# Buisnesscard.net
KiCad netlist of a schematic drawn in EasyEDA Pro
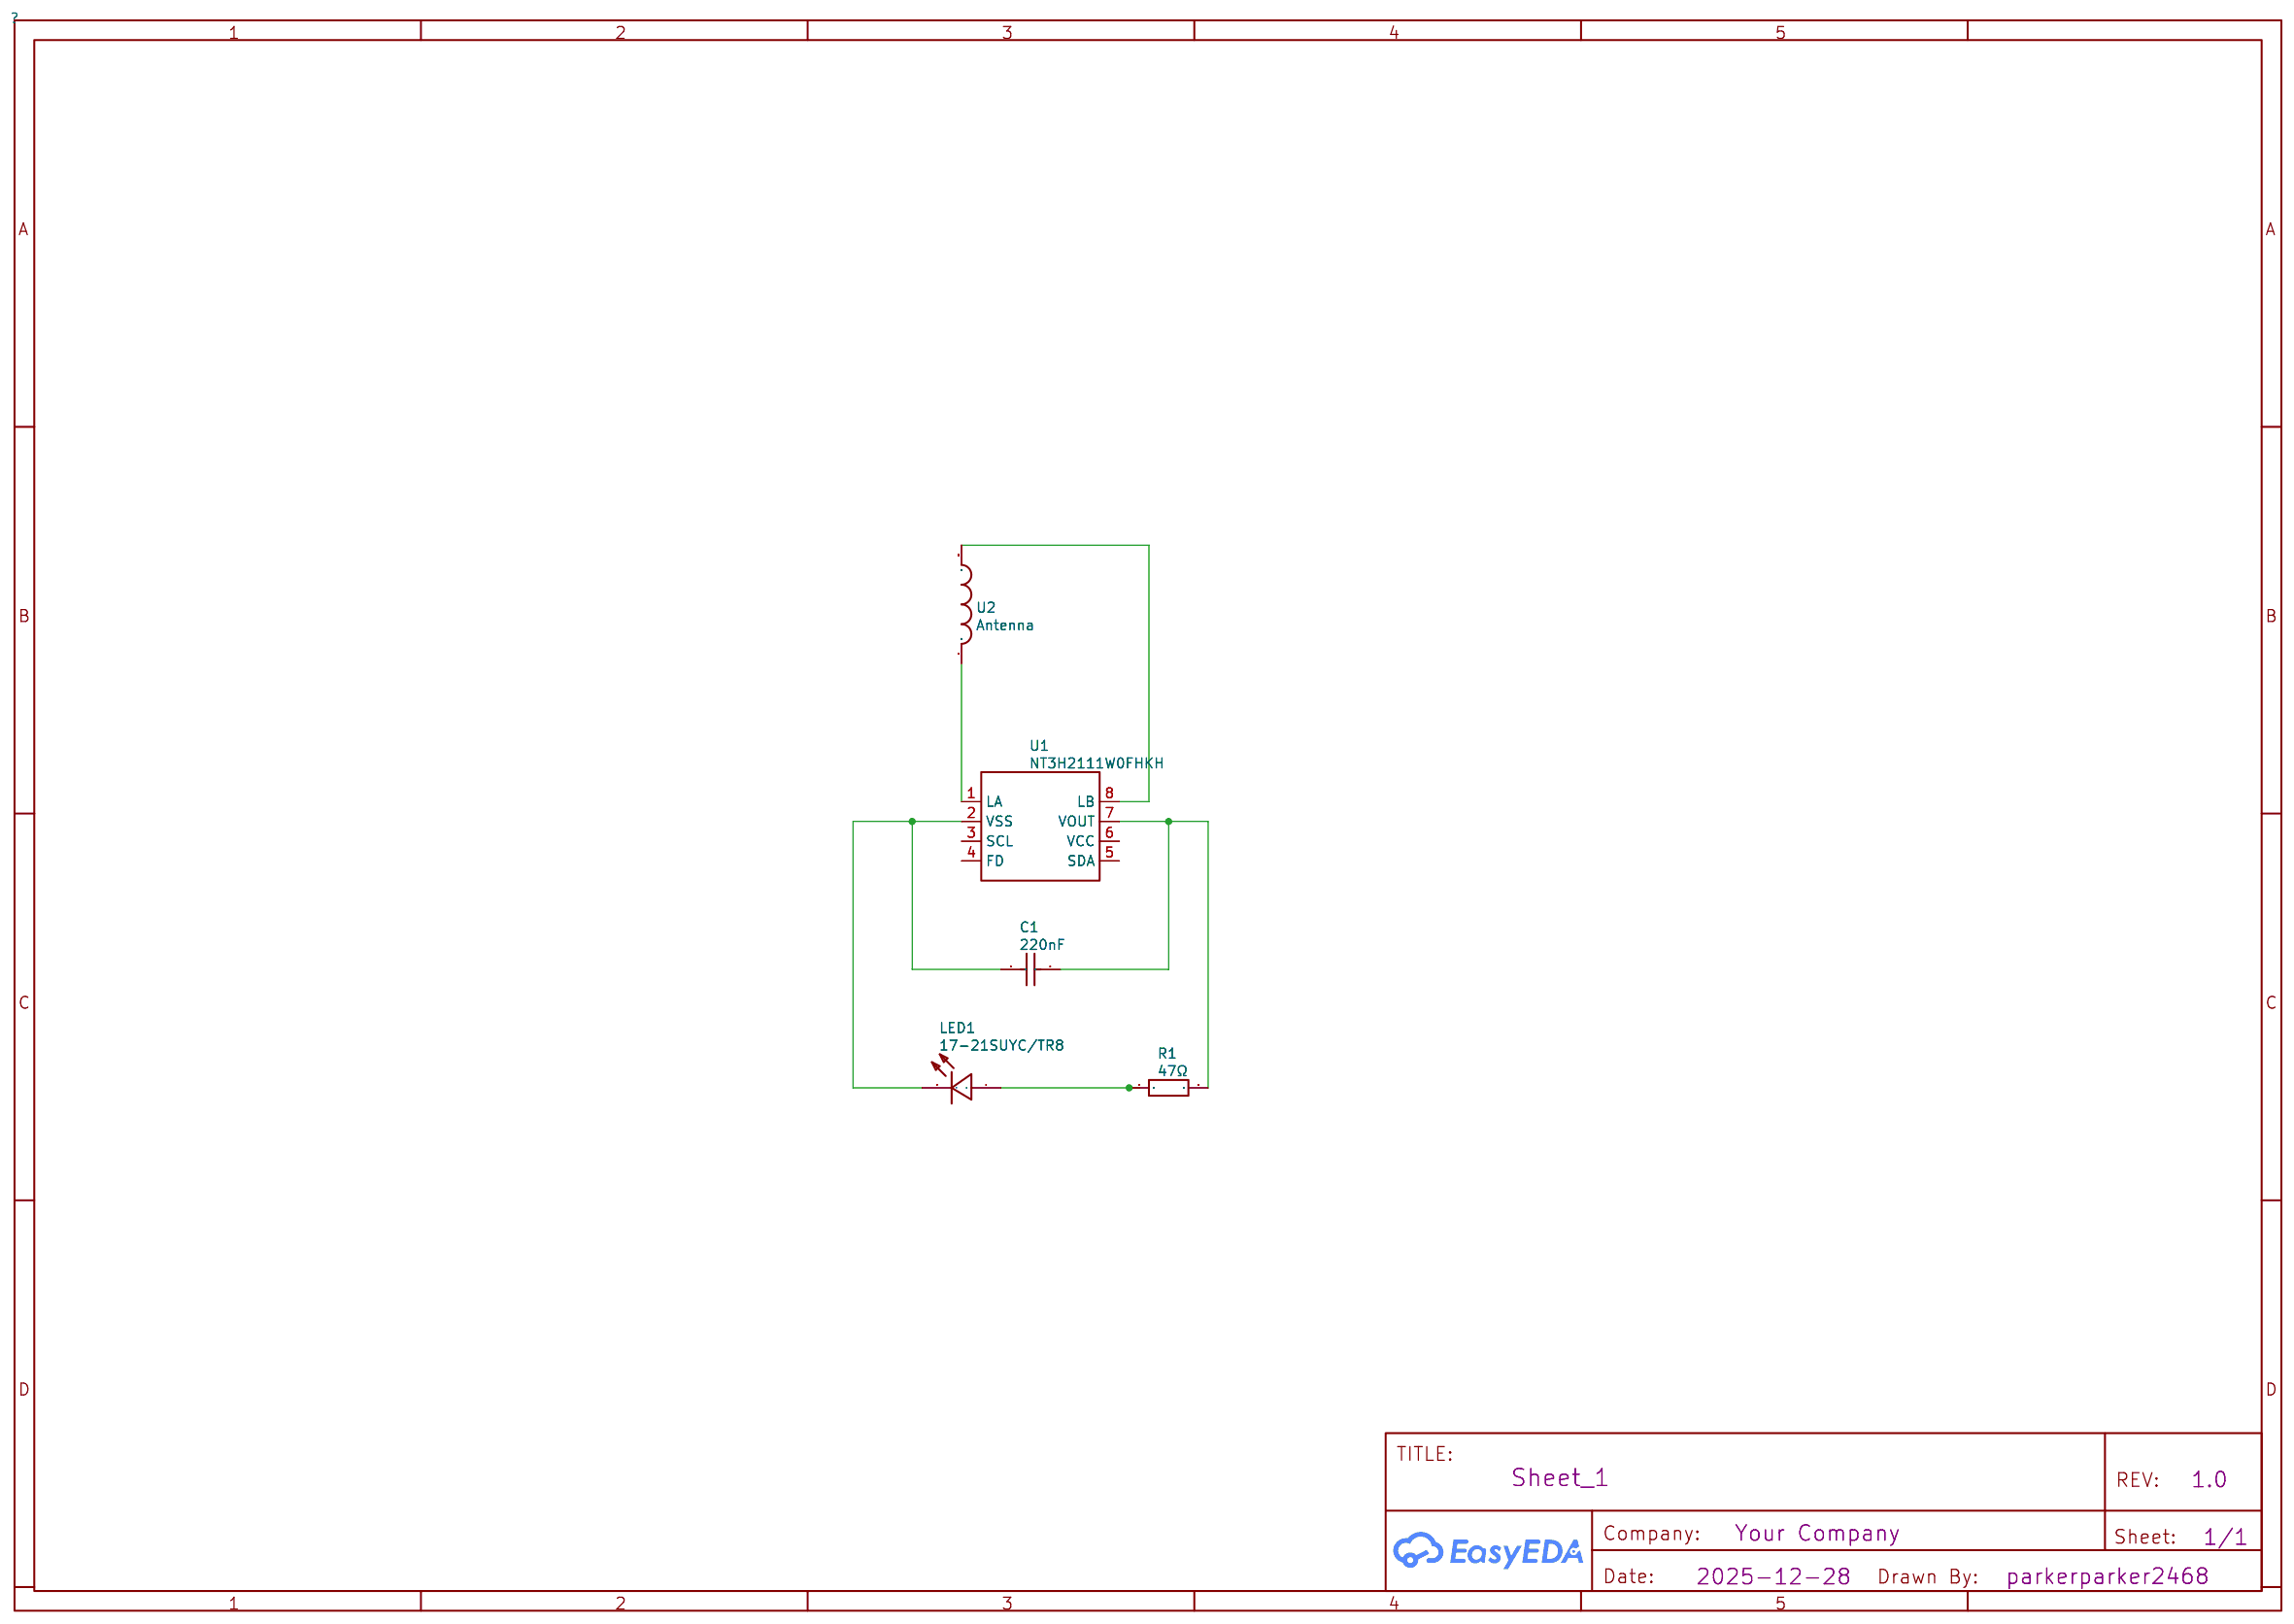
[diagram p0: schematic sheet]

(export (version "E")
  (design (tool "Eeschema 10.0.6"))
  (components
    (comp (ref "C1")
      (value "220nF")
      (footprint "easyedapro:C0603")
      (fields
        (field (name "Manufacturer Part") "CL10B224KA8NNNC")
        (field (name "Manufacturer") "SAMSUNG(三星)")
      )
      (libsource (lib "easyedapro") (part "220nF"))
    )
    (comp (ref "LED1")
      (value "17-21SUYC/TR8")
      (footprint "easyedapro:LED0805-R-RD")
      (fields (field (name "Manufacturer Part") "KT-0805黄灯") (field (name "Manufacturer") "KENTO"))
      (libsource (lib "easyedapro") (part "17-21SUYC/TR8"))
    )
    (comp (ref "R1")
      (value "47Ω")
      (footprint "easyedapro:R0603")
      (fields
        (field (name "Manufacturer Part") "0603WAF470JT5E")
        (field (name "Manufacturer") "UNI-ROYAL(厚声)")
      )
      (libsource (lib "easyedapro") (part "47Ω"))
    )
    (comp (ref "U1")
      (value "NT3H2111W0FHKH")
      (footprint "easyedapro:XQFN-8_L1.6-W1.6-P0.50-BL_NT3H2111W0FHKH")
      (fields (field (name "Manufacturer") "NXP(恩智浦)") (field (name "Contributor") "LCSC"))
      (libsource (lib "easyedapro") (part "NT3H2111W0FHKH"))
    )
    (comp (ref "U2")
      (value "Antenna")
      (footprint "easyedapro:25X48MM_NFC_ANTENNA")
      (fields (field (name "Contributor") "maggie.j.liu"))
      (libsource (lib "easyedapro") (part "Antenna"))
    )
  )
  (nets
    (net (code "1") (name "Net-(LED1-+)") (class "Default")
      (node (ref "LED1") (pin "1") (pinfunction "+_1") (pintype "unspecified"))
      (node (ref "R1") (pin "1") (pinfunction "1_1") (pintype "input"))
    )
    (net (code "2") (name "Net-(LED1--)") (class "Default")
      (node (ref "C1") (pin "1") (pinfunction "1_1") (pintype "input"))
      (node (ref "LED1") (pin "2") (pinfunction "-_2") (pintype "unspecified"))
      (node (ref "U1") (pin "2") (pinfunction "VSS_2") (pintype "unspecified"))
    )
    (net (code "3") (name "Net-(U1-LA)") (class "Default")
      (node (ref "U1") (pin "1") (pinfunction "LA_1") (pintype "unspecified"))
      (node (ref "U2") (pin "P$1") (pinfunction "P$1_P$1") (pintype "unspecified"))
    )
    (net (code "4") (name "Net-(U1-LB)") (class "Default")
      (node (ref "U1") (pin "8") (pinfunction "LB_8") (pintype "unspecified"))
      (node (ref "U2") (pin "P$2") (pinfunction "P$2_P$2") (pintype "unspecified"))
    )
    (net (code "5") (name "Net-(U1-VOUT)") (class "Default")
      (node (ref "C1") (pin "2") (pinfunction "2_2") (pintype "input"))
      (node (ref "R1") (pin "2") (pinfunction "2_2") (pintype "input"))
      (node (ref "U1") (pin "7") (pinfunction "VOUT_7") (pintype "unspecified"))
    )
    (net (code "6") (name "unconnected-(U1-FD-Pad4)") (class "Default")
      (node (ref "U1") (pin "4") (pinfunction "FD_4") (pintype "unspecified"))
    )
    (net (code "7") (name "unconnected-(U1-SCL-Pad3)") (class "Default")
      (node (ref "U1") (pin "3") (pinfunction "SCL_3") (pintype "unspecified"))
    )
    (net (code "8") (name "unconnected-(U1-SDA-Pad5)") (class "Default")
      (node (ref "U1") (pin "5") (pinfunction "SDA_5") (pintype "unspecified"))
    )
    (net (code "9") (name "unconnected-(U1-VCC-Pad6)") (class "Default")
      (node (ref "U1") (pin "6") (pinfunction "VCC_6") (pintype "unspecified"))
    )
  )
)
